# dps-relay.net
KiCad netlist of a schematic drawn in EAGLE
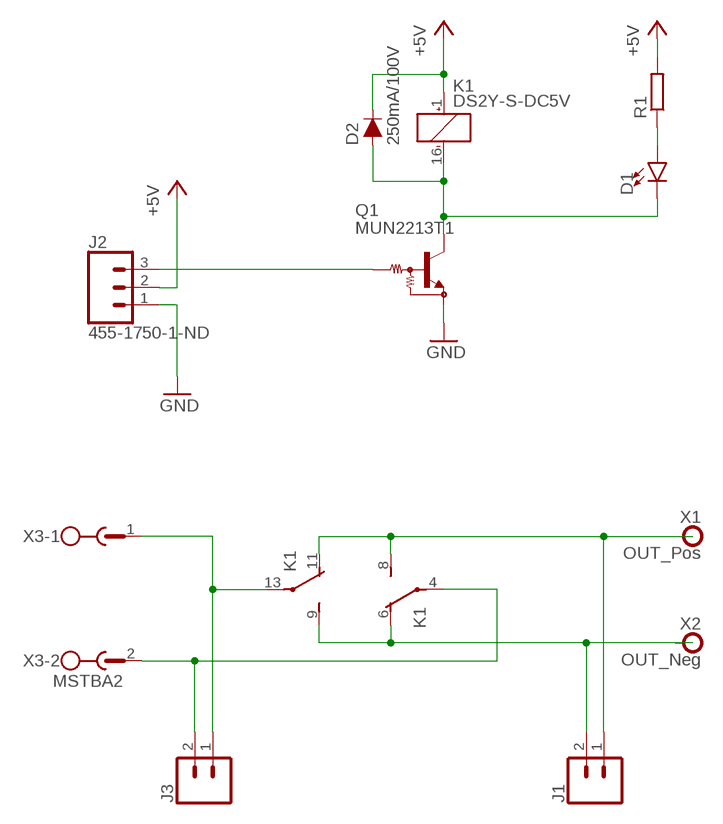
[diagram p0: schematic, sheet 1]

(export (version "E")
  (design (tool "Eeschema 10.0.6"))
  (components
    (comp (ref "D1")
      (value "LED3MM")
      (footprint "eagle-import:LED_3MM")
      (libsource (lib "eagle-import") (part "LED3MM"))
    )
    (comp (ref "D2")
      (value "250mA/100V")
      (footprint "eagle-import:SOD-323")
      (libsource (lib "eagle-import") (part "DIODE-BAS16J"))
    )
    (comp (ref "J1")
      (value "CONN_02")
      (footprint "eagle-import:1X02")
      (libsource (lib "eagle-import") (part "CONN_02"))
    )
    (comp (ref "J2")
      (value "455-1750-1-ND")
      (footprint "eagle-import:1X03")
      (libsource (lib "eagle-import") (part "CONN_03"))
    )
    (comp (ref "J3")
      (value "CONN_02")
      (footprint "eagle-import:1X02")
      (libsource (lib "eagle-import") (part "CONN_02"))
    )
    (comp (ref "K1")
      (value "DS2Y-S-DC5V")
      (footprint "eagle-import:DS2Y")
      (libsource (lib "eagle-import") (part "DS2Y-S-DC5V"))
    )
    (comp (ref "Q1")
      (value "MUN2213T1")
      (footprint "eagle-import:SC59-BEC")
      (libsource (lib "eagle-import") (part "MUN2213T1"))
    )
    (comp (ref "R1")
      (value "R-EU_R1206")
      (footprint "eagle-import:R1206")
      (libsource (lib "eagle-import") (part "R-EU_R1206"))
    )
    (comp (ref "X1")
      (value "OUT_Pos")
      (footprint "eagle-import:SOCKET_24.243")
      (libsource (lib "eagle-import") (part "SOCKET_24.243"))
    )
    (comp (ref "X2")
      (value "OUT_Neg")
      (footprint "eagle-import:SOCKET_24.243")
      (libsource (lib "eagle-import") (part "SOCKET_24.243"))
    )
    (comp (ref "X3")
      (value "MSTBA2")
      (footprint "eagle-import:MSTBA2")
      (fields (field (name "MF") "FARNELL") (field (name "MPN") "1757242"))
      (libsource (lib "eagle-import") (part "MSTBA2"))
    )
  )
  (nets
    (net (code "1") (name "+5V") (class "Default")
      (node (ref "D2") (pin "C") (pinfunction "C_C") (pintype "passive"))
      (node (ref "J2") (pin "2") (pinfunction "2_2") (pintype "passive"))
      (node (ref "K1") (pin "1") (pinfunction "+_1") (pintype "passive"))
      (node (ref "R1") (pin "2") (pinfunction "2_2") (pintype "passive"))
    )
    (net (code "2") (name "GND") (class "Default")
      (node (ref "J2") (pin "1") (pinfunction "1_1") (pintype "passive"))
      (node (ref "Q1") (pin "E") (pinfunction "E_E") (pintype "passive"))
    )
    (net (code "3") (name "Net-(D1-C)") (class "Default")
      (node (ref "D1") (pin "K") (pinfunction "C_K") (pintype "passive"))
      (node (ref "D2") (pin "A") (pinfunction "A_A") (pintype "passive"))
      (node (ref "K1") (pin "16") (pinfunction "-_16") (pintype "passive"))
      (node (ref "Q1") (pin "C") (pinfunction "C_C") (pintype "passive"))
    )
    (net (code "4") (name "Net-(D1-PadA)") (class "Default")
      (node (ref "D1") (pin "A") (pinfunction "A_A") (pintype "passive"))
      (node (ref "R1") (pin "1") (pinfunction "1_1") (pintype "passive"))
    )
    (net (code "5") (name "Net-(J2-Pad3)") (class "Default")
      (node (ref "J2") (pin "3") (pinfunction "3_3") (pintype "passive"))
      (node (ref "Q1") (pin "B") (pinfunction "B_B") (pintype "passive"))
    )
    (net (code "6") (name "Net-(K1B-O)") (class "Default")
      (node (ref "J1") (pin "2") (pinfunction "2_2") (pintype "passive"))
      (node (ref "K1") (pin "6") (pinfunction "O_6") (pintype "passive"))
      (node (ref "K1") (pin "9") (pinfunction "S_9") (pintype "passive"))
      (node (ref "X2") (pin "1") (pinfunction "P_1") (pintype "passive"))
      (node (ref "X2") (pin "2") (pinfunction "P_2") (pintype "passive"))
    )
    (net (code "7") (name "Net-(K1B-P)") (class "Default")
      (node (ref "J3") (pin "2") (pinfunction "2_2") (pintype "passive"))
      (node (ref "K1") (pin "4") (pinfunction "P_4") (pintype "passive"))
      (node (ref "X3") (pin "2") (pinfunction "1_2") (pintype "passive"))
    )
    (net (code "8") (name "Net-(K1B-S)") (class "Default")
      (node (ref "J1") (pin "1") (pinfunction "1_1") (pintype "passive"))
      (node (ref "K1") (pin "11") (pinfunction "O_11") (pintype "passive"))
      (node (ref "K1") (pin "8") (pinfunction "S_8") (pintype "passive"))
      (node (ref "X1") (pin "1") (pinfunction "P_1") (pintype "passive"))
      (node (ref "X1") (pin "2") (pinfunction "P_2") (pintype "passive"))
    )
    (net (code "9") (name "Net-(K1C-P)") (class "Default")
      (node (ref "J3") (pin "1") (pinfunction "1_1") (pintype "passive"))
      (node (ref "K1") (pin "13") (pinfunction "P_13") (pintype "passive"))
      (node (ref "X3") (pin "1") (pinfunction "1_1") (pintype "passive"))
    )
  )
)
